# 9_USB_Connectors.net
KiCad netlist of a schematic drawn in Altium Designer
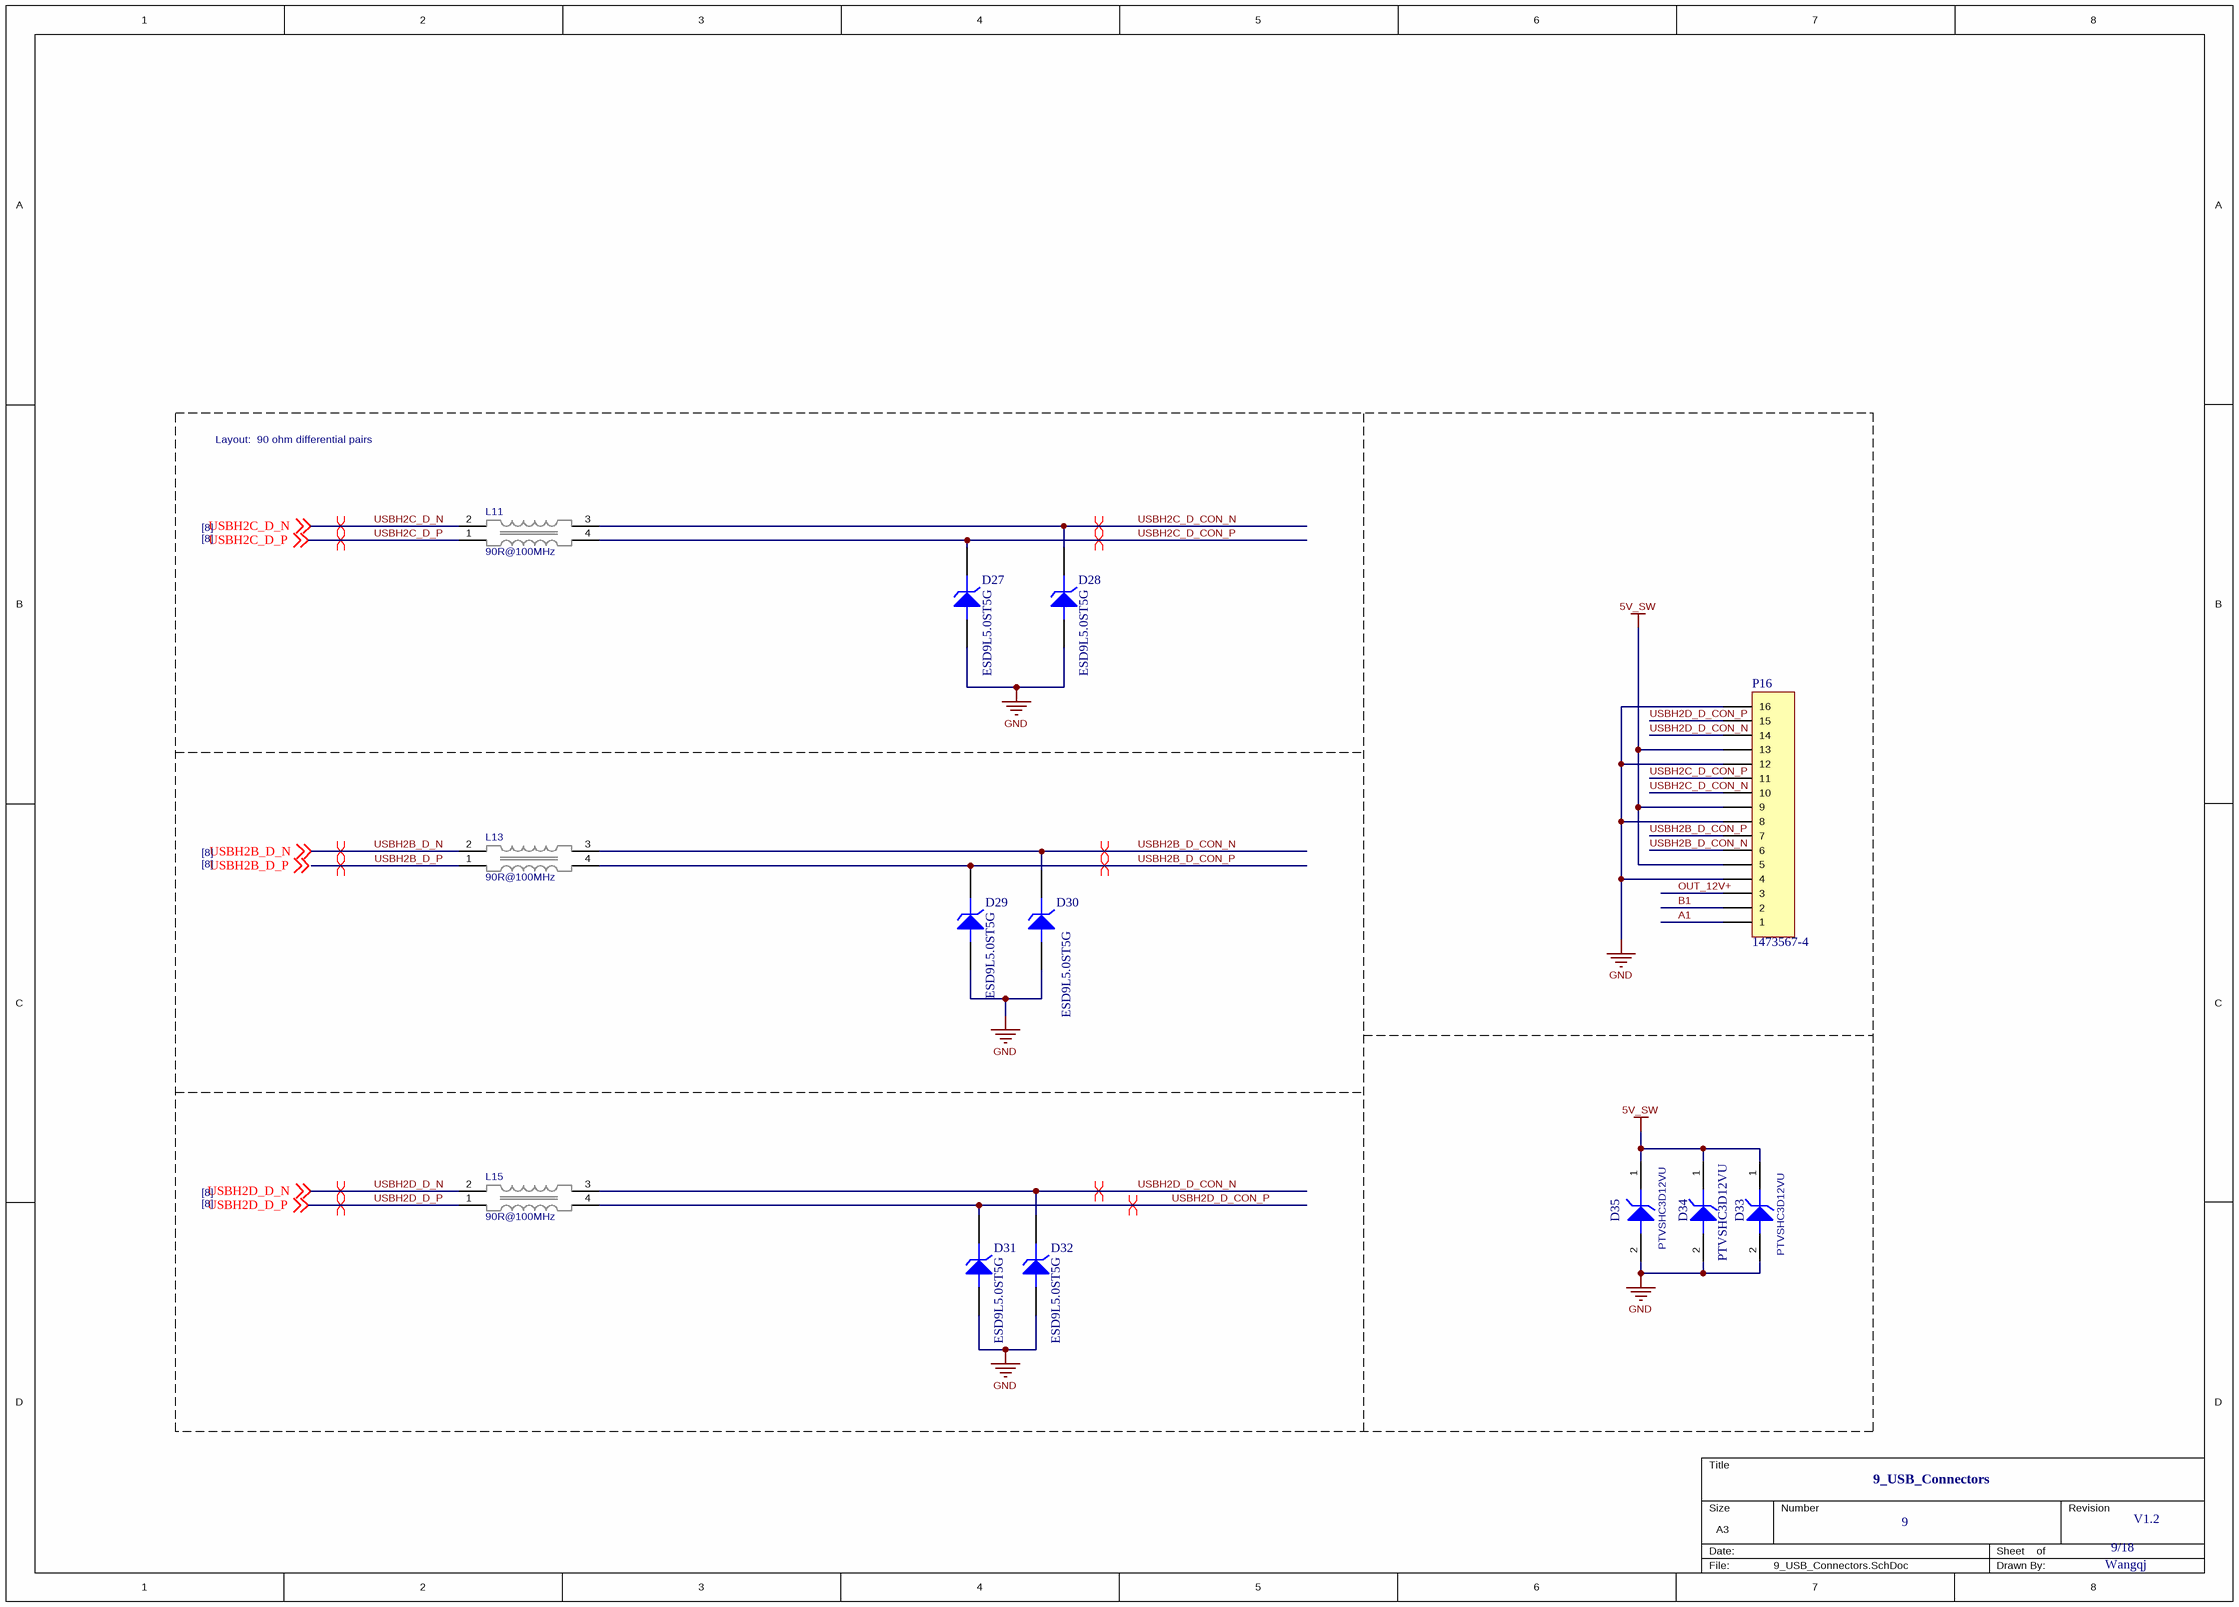
[diagram p0: 9_USB_Connectors.SchDoc]

(export (version "E")
  (design (tool "Eeschema 10.0.6"))
  (components
    (comp (ref "D27")
      (value "ESD9L5.0ST5G")
      (footprint "LC-SOD-923")
      (description "TVS Diode")
      (libsource (lib "二极管") (part "ZENER3"))
    )
    (comp (ref "D28")
      (value "ESD9L5.0ST5G")
      (footprint "LC-SOD-923")
      (description "TVS Diode")
      (libsource (lib "二极管") (part "ZENER3"))
    )
    (comp (ref "D29")
      (value "ESD9L5.0ST5G")
      (footprint "LC-SOD-923")
      (description "TVS Diode")
      (libsource (lib "二极管") (part "ZENER3"))
    )
    (comp (ref "D30")
      (value "ESD9L5.0ST5G")
      (footprint "LC-SOD-923")
      (description "TVS Diode")
      (libsource (lib "二极管") (part "ZENER3"))
    )
    (comp (ref "D31")
      (value "ESD9L5.0ST5G")
      (footprint "LC-SOD-923")
      (description "TVS Diode")
      (libsource (lib "二极管") (part "ZENER3"))
    )
    (comp (ref "D32")
      (value "ESD9L5.0ST5G")
      (footprint "LC-SOD-923")
      (description "TVS Diode")
      (libsource (lib "二极管") (part "ZENER3"))
    )
    (comp (ref "D33")
      (value "PTVSHC3D12VU")
      (footprint "LC-SOD-323")
      (description "TVS Diode")
      (libsource (lib "Apalis Evaluation Board") (part "Diode_TVS"))
    )
    (comp (ref "D34")
      (value "PTVSHC3D12VU")
      (footprint "LC-SOD-323")
      (description "TVS Diode")
      (libsource (lib "Apalis Evaluation Board") (part "Diode_TVS"))
    )
    (comp (ref "D35")
      (value "PTVSHC3D12VU")
      (footprint "LC-SOD-323")
      (description "TVS Diode")
      (libsource (lib "Apalis Evaluation Board") (part "Diode_TVS"))
    )
    (comp (ref "L11")
      (value "90R@100MHz")
      (footprint "T_Murata_DLW21SN900SQ2")
      (description "Common Mode Choke High Speed 90R 330mA")
      (fields (field (name "TOLERANCE") "25%") (field (name "MANUFACTURER PART NO.") "DLW21SN900SQ2"))
      (libsource (lib "Apalis Evaluation Board") (part "L-Murata-DLW21SN900SQ2-90R@100MHz-330mA-25%"))
    )
    (comp (ref "L13")
      (value "90R@100MHz")
      (footprint "T_Murata_DLW21SN900SQ2")
      (description "Common Mode Choke High Speed 90R 330mA")
      (fields (field (name "TOLERANCE") "25%") (field (name "MANUFACTURER PART NO.") "DLW21SN900SQ2"))
      (libsource (lib "Apalis Evaluation Board") (part "L-Murata-DLW21SN900SQ2-90R@100MHz-330mA-25%"))
    )
    (comp (ref "L15")
      (value "90R@100MHz")
      (footprint "T_Murata_DLW21SN900SQ2")
      (description "Common Mode Choke High Speed 90R 330mA")
      (fields (field (name "TOLERANCE") "25%") (field (name "MANUFACTURER PART NO.") "DLW21SN900SQ2"))
      (libsource (lib "Apalis Evaluation Board") (part "L-Murata-DLW21SN900SQ2-90R@100MHz-330mA-25%"))
    )
    (comp (ref "P16")
      (value "1473567-4")
      (footprint "147-4")
      (description "泰科4p端子")
      (fields (field (name "PUBLISHER") "Altium Limited"))
      (libsource (lib "Miscellaneous Connectors") (part "Header 16H"))
    )
  )
  (nets
    (net (code "1") (name "/A1") (class "Default")
      (node (ref "P16") (pin "1") (pinfunction "1_1") (pintype "passive"))
    )
    (net (code "2") (name "/B1") (class "Default")
      (node (ref "P16") (pin "2") (pinfunction "2_2") (pintype "passive"))
    )
    (net (code "3") (name "/OUT_12V+") (class "Default")
      (node (ref "P16") (pin "3") (pinfunction "3_3") (pintype "passive"))
    )
    (net (code "4") (name "/USBH2B_D_CON_N") (class "Default")
      (node (ref "D30") (pin "2") (pinfunction "K_2") (pintype "passive"))
      (node (ref "L13") (pin "3") (pinfunction "3_3") (pintype "passive"))
      (node (ref "P16") (pin "6") (pinfunction "6_6") (pintype "passive"))
    )
    (net (code "5") (name "/USBH2B_D_CON_P") (class "Default")
      (node (ref "D29") (pin "2") (pinfunction "K_2") (pintype "passive"))
      (node (ref "L13") (pin "4") (pinfunction "4_4") (pintype "passive"))
      (node (ref "P16") (pin "7") (pinfunction "7_7") (pintype "passive"))
    )
    (net (code "6") (name "/USBH2C_D_CON_N") (class "Default")
      (node (ref "D28") (pin "2") (pinfunction "K_2") (pintype "passive"))
      (node (ref "L11") (pin "3") (pinfunction "3_3") (pintype "passive"))
      (node (ref "P16") (pin "10") (pinfunction "10_10") (pintype "passive"))
    )
    (net (code "7") (name "/USBH2C_D_CON_P") (class "Default")
      (node (ref "D27") (pin "2") (pinfunction "K_2") (pintype "passive"))
      (node (ref "L11") (pin "4") (pinfunction "4_4") (pintype "passive"))
      (node (ref "P16") (pin "11") (pinfunction "11_11") (pintype "passive"))
    )
    (net (code "8") (name "/USBH2D_D_CON_N") (class "Default")
      (node (ref "D32") (pin "2") (pinfunction "K_2") (pintype "passive"))
      (node (ref "L15") (pin "3") (pinfunction "3_3") (pintype "passive"))
      (node (ref "P16") (pin "14") (pinfunction "14_14") (pintype "passive"))
    )
    (net (code "9") (name "/USBH2D_D_CON_P") (class "Default")
      (node (ref "D31") (pin "2") (pinfunction "K_2") (pintype "passive"))
      (node (ref "L15") (pin "4") (pinfunction "4_4") (pintype "passive"))
      (node (ref "P16") (pin "15") (pinfunction "15_15") (pintype "passive"))
    )
    (net (code "10") (name "5V_SW") (class "Default")
      (node (ref "D33") (pin "1") (pinfunction "K_1") (pintype "passive"))
      (node (ref "D34") (pin "1") (pinfunction "K_1") (pintype "passive"))
      (node (ref "D35") (pin "1") (pinfunction "K_1") (pintype "passive"))
      (node (ref "P16") (pin "13") (pinfunction "13_13") (pintype "passive"))
      (node (ref "P16") (pin "5") (pinfunction "5_5") (pintype "passive"))
      (node (ref "P16") (pin "9") (pinfunction "9_9") (pintype "passive"))
    )
    (net (code "11") (name "GND") (class "Default")
      (node (ref "D27") (pin "1") (pinfunction "A_1") (pintype "passive"))
      (node (ref "D28") (pin "1") (pinfunction "A_1") (pintype "passive"))
      (node (ref "D29") (pin "1") (pinfunction "A_1") (pintype "passive"))
      (node (ref "D30") (pin "1") (pinfunction "A_1") (pintype "passive"))
      (node (ref "D31") (pin "1") (pinfunction "A_1") (pintype "passive"))
      (node (ref "D32") (pin "1") (pinfunction "A_1") (pintype "passive"))
      (node (ref "D33") (pin "2") (pinfunction "A_2") (pintype "passive"))
      (node (ref "D34") (pin "2") (pinfunction "A_2") (pintype "passive"))
      (node (ref "D35") (pin "2") (pinfunction "A_2") (pintype "passive"))
      (node (ref "P16") (pin "12") (pinfunction "12_12") (pintype "passive"))
      (node (ref "P16") (pin "16") (pinfunction "16_16") (pintype "passive"))
      (node (ref "P16") (pin "4") (pinfunction "4_4") (pintype "passive"))
      (node (ref "P16") (pin "8") (pinfunction "8_8") (pintype "passive"))
    )
    (net (code "12") (name "USBH2B_D_N") (class "Default")
      (node (ref "L13") (pin "2") (pinfunction "2_2") (pintype "passive"))
    )
    (net (code "13") (name "USBH2B_D_P") (class "Default")
      (node (ref "L13") (pin "1") (pinfunction "1_1") (pintype "passive"))
    )
    (net (code "14") (name "USBH2C_D_N") (class "Default")
      (node (ref "L11") (pin "2") (pinfunction "2_2") (pintype "passive"))
    )
    (net (code "15") (name "USBH2C_D_P") (class "Default")
      (node (ref "L11") (pin "1") (pinfunction "1_1") (pintype "passive"))
    )
    (net (code "16") (name "USBH2D_D_N") (class "Default")
      (node (ref "L15") (pin "2") (pinfunction "2_2") (pintype "passive"))
    )
    (net (code "17") (name "USBH2D_D_P") (class "Default")
      (node (ref "L15") (pin "1") (pinfunction "1_1") (pintype "passive"))
    )
  )
)
